# TeamB_PDS.net
KiCad netlist of a schematic drawn in EAGLE
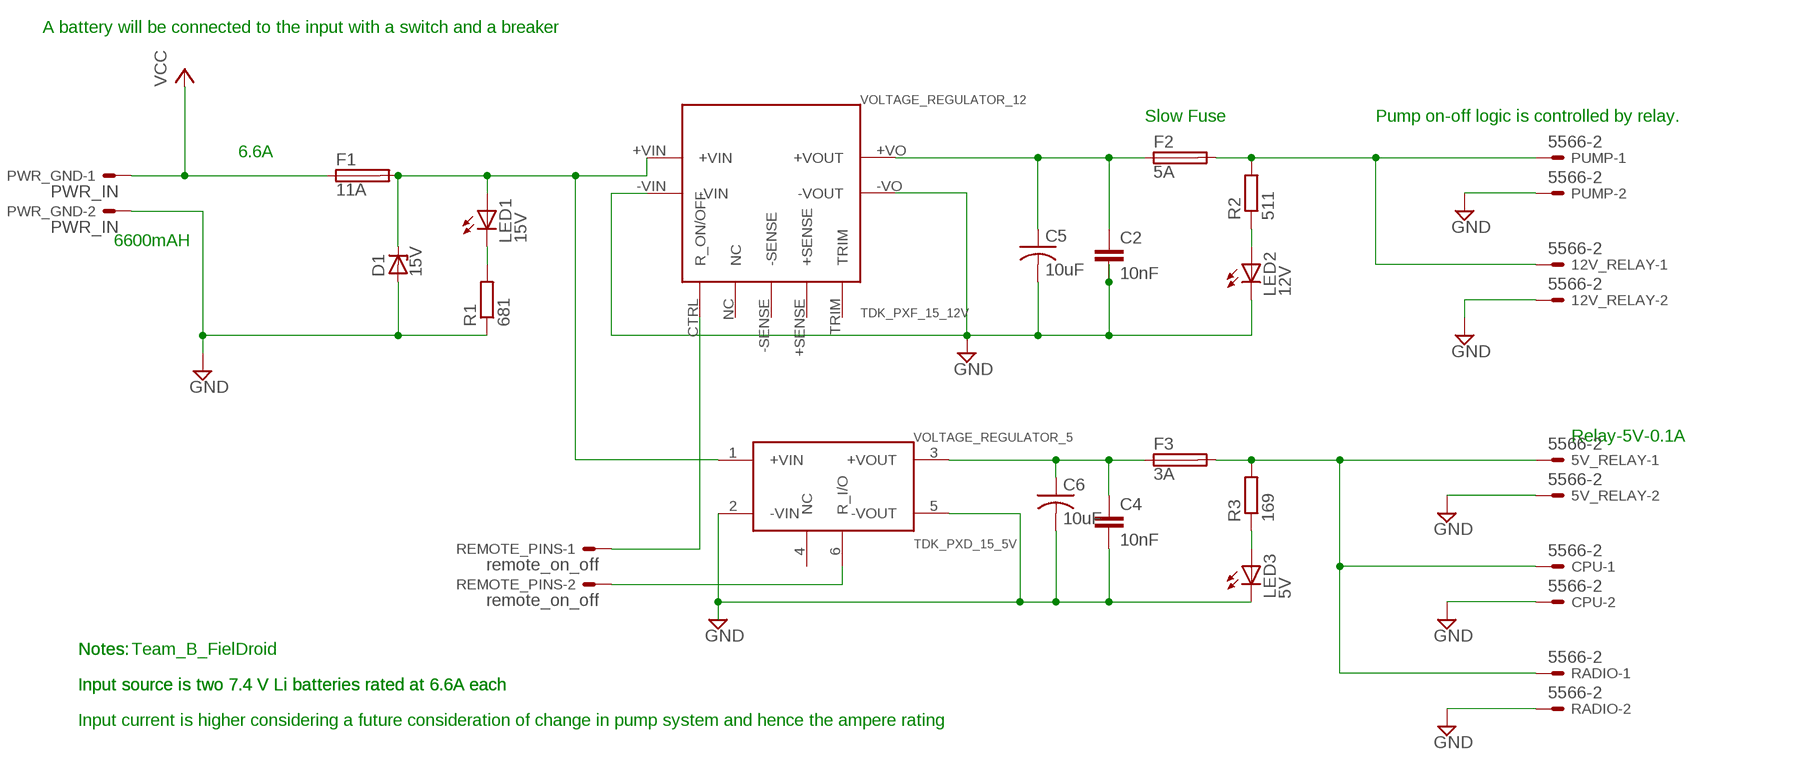
[diagram p0: schematic, sheet 1]

(export (version "E")
  (design (tool "Eeschema 10.0.6"))
  (components
    (comp (ref "5V_RELAY")
      (value "5566-2")
      (footprint "eagle-import:5566-2")
      (libsource (lib "eagle-import") (part "5566-2"))
    )
    (comp (ref "12V_RELAY")
      (value "5566-2")
      (footprint "eagle-import:5566-2")
      (libsource (lib "eagle-import") (part "5566-2"))
    )
    (comp (ref "C2")
      (value "10nF")
      (footprint "eagle-import:C2.5-4")
      (libsource (lib "eagle-import") (part "C2.5/4"))
    )
    (comp (ref "C4")
      (value "10nF")
      (footprint "eagle-import:C2.5-4")
      (libsource (lib "eagle-import") (part "C2.5/4"))
    )
    (comp (ref "C5")
      (value "10uF")
      (footprint "eagle-import:C050-024X044")
      (libsource (lib "eagle-import") (part "C-US050-024X044"))
    )
    (comp (ref "C6")
      (value "10uF")
      (footprint "eagle-import:C050-024X044")
      (libsource (lib "eagle-import") (part "C-US050-024X044"))
    )
    (comp (ref "CPU")
      (value "5566-2")
      (footprint "eagle-import:5566-2")
      (libsource (lib "eagle-import") (part "5566-2"))
    )
    (comp (ref "D1")
      (value "15V")
      (footprint "eagle-import:ZDIO-5")
      (libsource (lib "eagle-import") (part "ZENER-DIODEZD-5"))
    )
    (comp (ref "F1")
      (value "11A")
      (footprint "eagle-import:SH25")
      (fields (field (name "MF") "SCHURTER") (field (name "MPN") "0031.8211"))
      (libsource (lib "eagle-import") (part "SH25"))
    )
    (comp (ref "F2")
      (value "5A")
      (footprint "eagle-import:SH25")
      (fields (field (name "MF") "SCHURTER") (field (name "MPN") "0031.8211"))
      (libsource (lib "eagle-import") (part "SH25"))
    )
    (comp (ref "F3")
      (value "3A")
      (footprint "eagle-import:SH25")
      (fields (field (name "MF") "SCHURTER") (field (name "MPN") "0031.8211"))
      (libsource (lib "eagle-import") (part "SH25"))
    )
    (comp (ref "LED1")
      (value "15V")
      (footprint "eagle-import:LED5MM")
      (libsource (lib "eagle-import") (part "LED5MM"))
    )
    (comp (ref "LED2")
      (value "12V")
      (footprint "eagle-import:LED5MM")
      (libsource (lib "eagle-import") (part "LED5MM"))
    )
    (comp (ref "LED3")
      (value "5V")
      (footprint "eagle-import:LED5MM")
      (libsource (lib "eagle-import") (part "LED5MM"))
    )
    (comp (ref "PUMP")
      (value "5566-2")
      (footprint "eagle-import:5566-2")
      (libsource (lib "eagle-import") (part "5566-2"))
    )
    (comp (ref "PWR_GND")
      (value "PWR_IN")
      (footprint "eagle-import:5566-2")
      (libsource (lib "eagle-import") (part "5566-2"))
    )
    (comp (ref "R1")
      (value "681")
      (footprint "eagle-import:0204_7")
      (libsource (lib "eagle-import") (part "R-EU_0204/7"))
    )
    (comp (ref "R2")
      (value "511")
      (footprint "eagle-import:0204_7")
      (libsource (lib "eagle-import") (part "R-EU_0204/7"))
    )
    (comp (ref "R3")
      (value "169")
      (footprint "eagle-import:0204_7")
      (libsource (lib "eagle-import") (part "R-EU_0204/7"))
    )
    (comp (ref "RADIO")
      (value "5566-2")
      (footprint "eagle-import:5566-2")
      (libsource (lib "eagle-import") (part "5566-2"))
    )
    (comp (ref "REMOTE_PINS")
      (value "remote_on_off")
      (footprint "eagle-import:5566-2")
      (libsource (lib "eagle-import") (part "5566-2"))
    )
    (comp (ref "VOLTAGE_REGULATOR_5")
      (value "TDK_PXD_15_5V")
      (footprint "eagle-import:TDK-PXD_15-5V")
      (libsource (lib "eagle-import") (part "TDK_PXD_15_5V"))
    )
    (comp (ref "VOLTAGE_REGULATOR_12")
      (value "TDK_PXF_15_12V")
      (footprint "eagle-import:TDK_PXF_15_12V")
      (libsource (lib "eagle-import") (part "TDK_PXF_15_12V"))
    )
  )
  (nets
    (net (code "1") (name "GND") (class "Default")
      (node (ref "12V_RELAY") (pin "2") (pinfunction "S_2") (pintype "passive"))
      (node (ref "5V_RELAY") (pin "2") (pinfunction "S_2") (pintype "passive"))
      (node (ref "C2") (pin "2") (pinfunction "2_2") (pintype "passive"))
      (node (ref "C4") (pin "2") (pinfunction "2_2") (pintype "passive"))
      (node (ref "C5") (pin "2") (pinfunction "2_2") (pintype "passive"))
      (node (ref "C6") (pin "2") (pinfunction "2_2") (pintype "passive"))
      (node (ref "CPU") (pin "2") (pinfunction "S_2") (pintype "passive"))
      (node (ref "D1") (pin "A") (pinfunction "A_A") (pintype "passive"))
      (node (ref "LED2") (pin "K") (pinfunction "C_K") (pintype "passive"))
      (node (ref "LED3") (pin "K") (pinfunction "C_K") (pintype "passive"))
      (node (ref "PUMP") (pin "2") (pinfunction "S_2") (pintype "passive"))
      (node (ref "PWR_GND") (pin "2") (pinfunction "S_2") (pintype "passive"))
      (node (ref "R1") (pin "1") (pinfunction "1_1") (pintype "passive"))
      (node (ref "RADIO") (pin "2") (pinfunction "S_2") (pintype "passive"))
      (node (ref "VOLTAGE_REGULATOR_12") (pin "-VIN") (pinfunction "-VIN_-VIN") (pintype "bidirectional"))
      (node (ref "VOLTAGE_REGULATOR_12") (pin "-VO") (pinfunction "-VOUT_-VO") (pintype "bidirectional"))
      (node (ref "VOLTAGE_REGULATOR_5") (pin "2") (pinfunction "-VIN_2") (pintype "bidirectional"))
      (node (ref "VOLTAGE_REGULATOR_5") (pin "5") (pinfunction "-VOUT_5") (pintype "bidirectional"))
    )
    (net (code "2") (name "Net-(5V_RELAYA-S)") (class "Default")
      (node (ref "5V_RELAY") (pin "1") (pinfunction "S_1") (pintype "passive"))
      (node (ref "CPU") (pin "1") (pinfunction "S_1") (pintype "passive"))
      (node (ref "F3") (pin "2") (pinfunction "2_2") (pintype "passive"))
      (node (ref "R3") (pin "2") (pinfunction "2_2") (pintype "passive"))
      (node (ref "RADIO") (pin "1") (pinfunction "S_1") (pintype "passive"))
    )
    (net (code "3") (name "Net-(12V_RELAYA-S)") (class "Default")
      (node (ref "12V_RELAY") (pin "1") (pinfunction "S_1") (pintype "passive"))
      (node (ref "F2") (pin "2") (pinfunction "2_2") (pintype "passive"))
      (node (ref "PUMP") (pin "1") (pinfunction "S_1") (pintype "passive"))
      (node (ref "R2") (pin "2") (pinfunction "2_2") (pintype "passive"))
    )
    (net (code "4") (name "Net-(LED1-C)") (class "Default")
      (node (ref "LED1") (pin "K") (pinfunction "C_K") (pintype "passive"))
      (node (ref "R1") (pin "2") (pinfunction "2_2") (pintype "passive"))
    )
    (net (code "5") (name "Net-(LED2-PadA)") (class "Default")
      (node (ref "LED2") (pin "A") (pinfunction "A_A") (pintype "passive"))
      (node (ref "R2") (pin "1") (pinfunction "1_1") (pintype "passive"))
    )
    (net (code "6") (name "Net-(LED3-PadA)") (class "Default")
      (node (ref "LED3") (pin "A") (pinfunction "A_A") (pintype "passive"))
      (node (ref "R3") (pin "1") (pinfunction "1_1") (pintype "passive"))
    )
    (net (code "7") (name "Net-(REMOTE_PINSA-S)") (class "Default")
      (node (ref "REMOTE_PINS") (pin "1") (pinfunction "S_1") (pintype "passive"))
      (node (ref "VOLTAGE_REGULATOR_12") (pin "CTRL") (pinfunction "R_ON/OFF_CTRL") (pintype "bidirectional"))
    )
    (net (code "8") (name "Net-(REMOTE_PINSB-S)") (class "Default")
      (node (ref "REMOTE_PINS") (pin "2") (pinfunction "S_2") (pintype "passive"))
      (node (ref "VOLTAGE_REGULATOR_5") (pin "6") (pinfunction "R_I/O_6") (pintype "bidirectional"))
    )
    (net (code "9") (name "Net-(VOLTAGE_REGULATOR_5-+VIN)") (class "Default")
      (node (ref "D1") (pin "C") (pinfunction "C_C") (pintype "passive"))
      (node (ref "F1") (pin "2") (pinfunction "2_2") (pintype "passive"))
      (node (ref "LED1") (pin "A") (pinfunction "A_A") (pintype "passive"))
      (node (ref "VOLTAGE_REGULATOR_12") (pin "+VIN") (pinfunction "+VIN_+VIN") (pintype "bidirectional"))
      (node (ref "VOLTAGE_REGULATOR_5") (pin "1") (pinfunction "+VIN_1") (pintype "bidirectional"))
    )
    (net (code "10") (name "Net-(VOLTAGE_REGULATOR_5-+VOUT)") (class "Default")
      (node (ref "C4") (pin "1") (pinfunction "1_1") (pintype "passive"))
      (node (ref "C6") (pin "1") (pinfunction "1_1") (pintype "passive"))
      (node (ref "F3") (pin "1") (pinfunction "1_1") (pintype "passive"))
      (node (ref "VOLTAGE_REGULATOR_5") (pin "3") (pinfunction "+VOUT_3") (pintype "bidirectional"))
    )
    (net (code "11") (name "Net-(VOLTAGE_REGULATOR_12-+VOUT)") (class "Default")
      (node (ref "C2") (pin "1") (pinfunction "1_1") (pintype "passive"))
      (node (ref "C5") (pin "1") (pinfunction "1_1") (pintype "passive"))
      (node (ref "F2") (pin "1") (pinfunction "1_1") (pintype "passive"))
      (node (ref "VOLTAGE_REGULATOR_12") (pin "+VO") (pinfunction "+VOUT_+VO") (pintype "bidirectional"))
    )
    (net (code "12") (name "VCC") (class "Default")
      (node (ref "F1") (pin "1") (pinfunction "1_1") (pintype "passive"))
      (node (ref "PWR_GND") (pin "1") (pinfunction "S_1") (pintype "passive"))
    )
    (net (code "13") (name "unconnected-(VOLTAGE_REGULATOR_5-NC-Pad4)") (class "Default")
      (node (ref "VOLTAGE_REGULATOR_5") (pin "4") (pinfunction "NC_4") (pintype "no_connect"))
    )
    (net (code "14") (name "unconnected-(VOLTAGE_REGULATOR_12-Pad+SENSE)") (class "Default")
      (node (ref "VOLTAGE_REGULATOR_12") (pin "+SENSE") (pinfunction "+SENSE_+SENSE") (pintype "bidirectional"))
    )
    (net (code "15") (name "unconnected-(VOLTAGE_REGULATOR_12-Pad-SENSE)") (class "Default")
      (node (ref "VOLTAGE_REGULATOR_12") (pin "-SENSE") (pinfunction "-SENSE_-SENSE") (pintype "bidirectional"))
    )
    (net (code "16") (name "unconnected-(VOLTAGE_REGULATOR_12-PadNC)") (class "Default")
      (node (ref "VOLTAGE_REGULATOR_12") (pin "NC") (pinfunction "NC_NC") (pintype "no_connect"))
    )
    (net (code "17") (name "unconnected-(VOLTAGE_REGULATOR_12-PadTRIM)") (class "Default")
      (node (ref "VOLTAGE_REGULATOR_12") (pin "TRIM") (pinfunction "TRIM_TRIM") (pintype "bidirectional"))
    )
  )
)
